# Clocking.net
KiCad netlist of a schematic drawn in Altium Designer
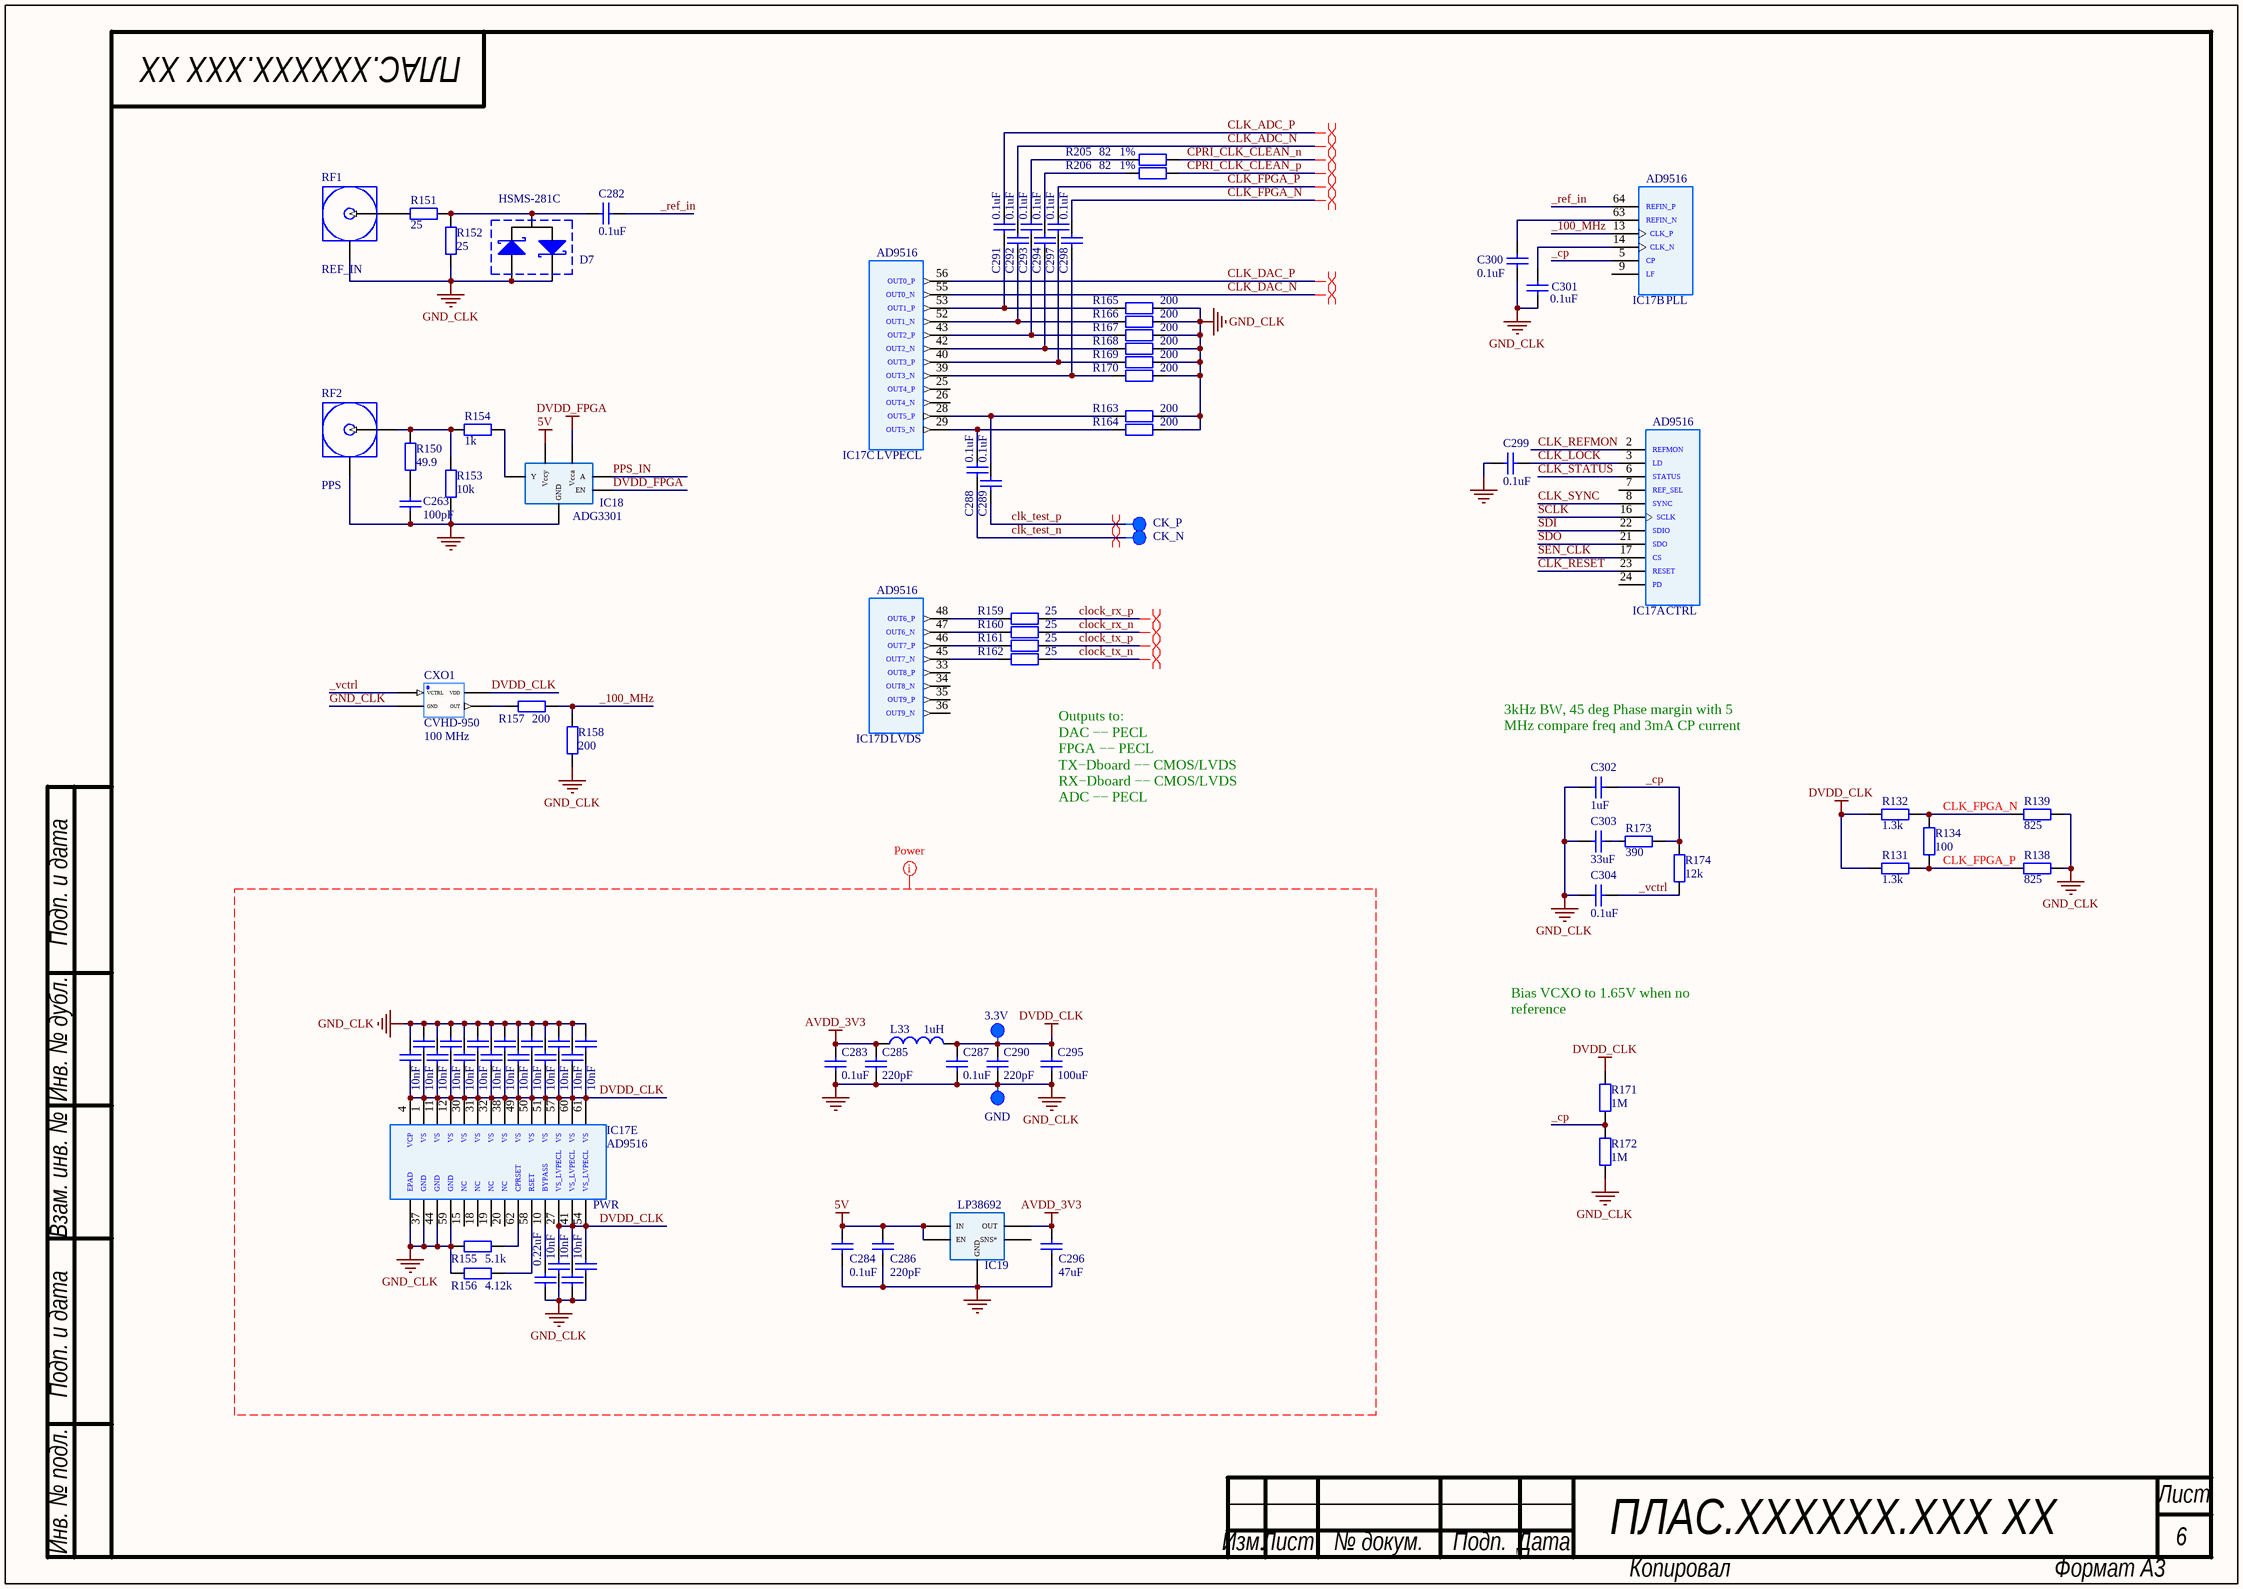
[diagram p0: Clocking.SchDoc]

(export (version "E")
  (design (tool "Eeschema 10.0.6"))
  (components
    (comp (ref "C263")
      (value "100pF")
      (footprint "С0402")
      (description "Cer Cap Small")
      (fields (field (name "MANUFACTURER") "Murata") (field (name "VOLTAGE") "16V"))
      (libsource (lib "") (part "Cer Cap_1"))
    )
    (comp (ref "C264")
      (value "10nF")
      (footprint "С0402")
      (description "Cer Cap Small")
      (fields (field (name "MANUFACTURER") "Murata") (field (name "VOLTAGE") "25V"))
      (libsource (lib "USRP2_Clone") (part "Cer Cap"))
    )
    (comp (ref "C265")
      (value "10nF")
      (footprint "С0402")
      (description "Cer Cap Small")
      (fields (field (name "MANUFACTURER") "Murata") (field (name "VOLTAGE") "25V"))
      (libsource (lib "USRP2_Clone") (part "Cer Cap"))
    )
    (comp (ref "C266")
      (value "10nF")
      (footprint "С0402")
      (description "Cer Cap Small")
      (fields (field (name "MANUFACTURER") "Murata") (field (name "VOLTAGE") "25V"))
      (libsource (lib "USRP2_Clone") (part "Cer Cap"))
    )
    (comp (ref "C267")
      (value "10nF")
      (footprint "С0402")
      (description "Cer Cap Small")
      (fields (field (name "MANUFACTURER") "Murata") (field (name "VOLTAGE") "25V"))
      (libsource (lib "USRP2_Clone") (part "Cer Cap"))
    )
    (comp (ref "C268")
      (value "10nF")
      (footprint "С0402")
      (description "Cer Cap Small")
      (fields (field (name "MANUFACTURER") "Murata") (field (name "VOLTAGE") "25V"))
      (libsource (lib "USRP2_Clone") (part "Cer Cap"))
    )
    (comp (ref "C269")
      (value "10nF")
      (footprint "С0402")
      (description "Cer Cap Small")
      (fields (field (name "MANUFACTURER") "Murata") (field (name "VOLTAGE") "25V"))
      (libsource (lib "USRP2_Clone") (part "Cer Cap"))
    )
    (comp (ref "C270")
      (value "10nF")
      (footprint "С0402")
      (description "Cer Cap Small")
      (fields (field (name "MANUFACTURER") "Murata") (field (name "VOLTAGE") "25V"))
      (libsource (lib "USRP2_Clone") (part "Cer Cap"))
    )
    (comp (ref "C271")
      (value "10nF")
      (footprint "С0402")
      (description "Cer Cap Small")
      (fields (field (name "MANUFACTURER") "Murata") (field (name "VOLTAGE") "25V"))
      (libsource (lib "USRP2_Clone") (part "Cer Cap"))
    )
    (comp (ref "C272")
      (value "10nF")
      (footprint "С0402")
      (description "Cer Cap Small")
      (fields (field (name "MANUFACTURER") "Murata") (field (name "VOLTAGE") "25V"))
      (libsource (lib "USRP2_Clone") (part "Cer Cap"))
    )
    (comp (ref "C273")
      (value "10nF")
      (footprint "С0402")
      (description "Cer Cap Small")
      (fields (field (name "MANUFACTURER") "Murata") (field (name "VOLTAGE") "25V"))
      (libsource (lib "USRP2_Clone") (part "Cer Cap"))
    )
    (comp (ref "C274")
      (value "10nF")
      (footprint "С0402")
      (description "Cer Cap Small")
      (fields (field (name "MANUFACTURER") "Murata") (field (name "VOLTAGE") "25V"))
      (libsource (lib "USRP2_Clone") (part "Cer Cap"))
    )
    (comp (ref "C275")
      (value "0.22uF")
      (footprint "С0402")
      (description "Cer Cap Small")
      (fields (field (name "MANUFACTURER") "Murata") (field (name "VOLTAGE") "16V"))
      (libsource (lib "USRP2_Clone") (part "Cer Cap"))
    )
    (comp (ref "C276")
      (value "10nF")
      (footprint "С0402")
      (description "Cer Cap Small")
      (fields (field (name "MANUFACTURER") "Murata") (field (name "VOLTAGE") "25V"))
      (libsource (lib "USRP2_Clone") (part "Cer Cap"))
    )
    (comp (ref "C277")
      (value "10nF")
      (footprint "С0402")
      (description "Cer Cap Small")
      (fields (field (name "MANUFACTURER") "Murata") (field (name "VOLTAGE") "25V"))
      (libsource (lib "USRP2_Clone") (part "Cer Cap"))
    )
    (comp (ref "C278")
      (value "10nF")
      (footprint "С0402")
      (description "Cer Cap Small")
      (fields (field (name "MANUFACTURER") "Murata") (field (name "VOLTAGE") "25V"))
      (libsource (lib "USRP2_Clone") (part "Cer Cap"))
    )
    (comp (ref "C279")
      (value "10nF")
      (footprint "С0402")
      (description "Cer Cap Small")
      (fields (field (name "MANUFACTURER") "Murata") (field (name "VOLTAGE") "25V"))
      (libsource (lib "USRP2_Clone") (part "Cer Cap"))
    )
    (comp (ref "C280")
      (value "10nF")
      (footprint "С0402")
      (description "Cer Cap Small")
      (fields (field (name "MANUFACTURER") "Murata") (field (name "VOLTAGE") "25V"))
      (libsource (lib "USRP2_Clone") (part "Cer Cap"))
    )
    (comp (ref "C281")
      (value "10nF")
      (footprint "С0402")
      (description "Cer Cap Small")
      (fields (field (name "MANUFACTURER") "Murata") (field (name "VOLTAGE") "25V"))
      (libsource (lib "USRP2_Clone") (part "Cer Cap"))
    )
    (comp (ref "C282")
      (value "0.1uF")
      (footprint "С0402")
      (description "Cer Cap Small")
      (fields (field (name "MANUFACTURER") "Murata") (field (name "VOLTAGE") "16V"))
      (libsource (lib "") (part "Cer Cap_1"))
    )
    (comp (ref "C283")
      (value "0.1uF")
      (footprint "C0603")
      (description "Cer Cap Small")
      (fields (field (name "MANUFACTURER") "Murata") (field (name "VOLTAGE") "16V"))
      (libsource (lib "USRP2_Clone") (part "Cer Cap"))
    )
    (comp (ref "C284")
      (value "0.1uF")
      (footprint "C0603")
      (description "Cer Cap Small")
      (fields (field (name "MANUFACTURER") "Murata") (field (name "VOLTAGE") "16V"))
      (libsource (lib "USRP2_Clone") (part "Cer Cap"))
    )
    (comp (ref "C285")
      (value "220pF")
      (footprint "C0603")
      (description "Cer Cap Small")
      (fields (field (name "MANUFACTURER") "Murata") (field (name "VOLTAGE") "16V"))
      (libsource (lib "USRP2_Clone") (part "Cer Cap"))
    )
    (comp (ref "C286")
      (value "220pF")
      (footprint "C0603")
      (description "Cer Cap Small")
      (fields (field (name "MANUFACTURER") "Murata") (field (name "VOLTAGE") "16V"))
      (libsource (lib "USRP2_Clone") (part "Cer Cap"))
    )
    (comp (ref "C287")
      (value "0.1uF")
      (footprint "C0603")
      (description "Cer Cap Small")
      (fields (field (name "MANUFACTURER") "Murata") (field (name "VOLTAGE") "16V"))
      (libsource (lib "USRP2_Clone") (part "Cer Cap"))
    )
    (comp (ref "C288")
      (value "0.1uF")
      (footprint "С0402")
      (description "Cer Cap Small")
      (fields (field (name "MANUFACTURER") "Murata") (field (name "VOLTAGE") "16V"))
      (libsource (lib "") (part "Cer Cap_1"))
    )
    (comp (ref "C289")
      (value "0.1uF")
      (footprint "С0402")
      (description "Cer Cap Small")
      (fields (field (name "MANUFACTURER") "Murata") (field (name "VOLTAGE") "16V"))
      (libsource (lib "") (part "Cer Cap_1"))
    )
    (comp (ref "C290")
      (value "220pF")
      (footprint "C0603")
      (description "Cer Cap Small")
      (fields (field (name "MANUFACTURER") "Murata") (field (name "VOLTAGE") "16V"))
      (libsource (lib "USRP2_Clone") (part "Cer Cap"))
    )
    (comp (ref "C291")
      (value "0.1uF")
      (footprint "С0402")
      (description "Cer Cap Small")
      (fields (field (name "MANUFACTURER") "Murata") (field (name "VOLTAGE") "16V"))
      (libsource (lib "") (part "Cer Cap_1"))
    )
    (comp (ref "C292")
      (value "0.1uF")
      (footprint "С0402")
      (description "Cer Cap Small")
      (fields (field (name "MANUFACTURER") "Murata") (field (name "VOLTAGE") "16V"))
      (libsource (lib "") (part "Cer Cap_1"))
    )
    (comp (ref "C293")
      (value "0.1uF")
      (footprint "С0402")
      (description "Cer Cap Small")
      (fields (field (name "MANUFACTURER") "Murata") (field (name "VOLTAGE") "16V"))
      (libsource (lib "") (part "Cer Cap_1"))
    )
    (comp (ref "C294")
      (value "0.1uF")
      (footprint "С0402")
      (description "Cer Cap Small")
      (fields (field (name "MANUFACTURER") "Murata") (field (name "VOLTAGE") "16V"))
      (libsource (lib "") (part "Cer Cap_1"))
    )
    (comp (ref "C295")
      (value "100uF")
      (footprint "C1210")
      (description "Cer Cap Large")
      (fields (field (name "MANUFACTURER") "Murata") (field (name "TOLERANCE") "20%"))
      (libsource (lib "") (part "Cap uF_1"))
    )
    (comp (ref "C296")
      (value "47uF")
      (footprint "C1210")
      (description "Cer Cap Large")
      (fields (field (name "MANUFACTURER") "Murata") (field (name "TOLERANCE") "20%"))
      (libsource (lib "USRP2_Clone") (part "Cap uF"))
    )
    (comp (ref "C297")
      (value "0.1uF")
      (footprint "С0402")
      (description "Cer Cap Small")
      (fields (field (name "MANUFACTURER") "Murata") (field (name "VOLTAGE") "16V"))
      (libsource (lib "") (part "Cer Cap_1"))
    )
    (comp (ref "C298")
      (value "0.1uF")
      (footprint "С0402")
      (description "Cer Cap Small")
      (fields (field (name "MANUFACTURER") "Murata") (field (name "VOLTAGE") "16V"))
      (libsource (lib "") (part "Cer Cap_1"))
    )
    (comp (ref "C299")
      (value "0.1uF")
      (footprint "С0402")
      (description "Cer Cap Small")
      (fields (field (name "MANUFACTURER") "Murata") (field (name "VOLTAGE") "16V"))
      (libsource (lib "USRP2_Clone") (part "Cer Cap"))
    )
    (comp (ref "C300")
      (value "0.1uF")
      (footprint "С0402")
      (description "Cer Cap Small")
      (fields (field (name "MANUFACTURER") "Murata") (field (name "VOLTAGE") "16V"))
      (libsource (lib "") (part "Cer Cap_1"))
    )
    (comp (ref "C301")
      (value "0.1uF")
      (footprint "С0402")
      (description "Cer Cap Small")
      (fields (field (name "MANUFACTURER") "Murata") (field (name "VOLTAGE") "16V"))
      (libsource (lib "USRP2_Clone") (part "Cer Cap"))
    )
    (comp (ref "C302")
      (value "1uF")
      (footprint "C0603")
      (description "Cer Cap Small")
      (fields (field (name "MANUFACTURER") "Murata") (field (name "VOLTAGE") "10V"))
      (libsource (lib "USRP2_Clone") (part "Cer Cap"))
    )
    (comp (ref "C303")
      (value "33uF")
      (footprint "C1210")
      (description "Cer Cap Large")
      (fields (field (name "MANUFACTURER") "Murata") (field (name "TOLERANCE") "20%"))
      (libsource (lib "USRP2_Clone") (part "Cap uF"))
    )
    (comp (ref "C304")
      (value "0.1uF")
      (footprint "C0603")
      (description "Cer Cap Small")
      (fields (field (name "MANUFACTURER") "Murata") (field (name "VOLTAGE") "16V"))
      (libsource (lib "USRP2_Clone") (part "Cer Cap"))
    )
    (comp (ref "CP9")
      (value "3.3V")
      (footprint "Control Point")
      (description "Control Point")
      (libsource (lib "USRP2_Clone") (part "Control Point"))
    )
    (comp (ref "CP10")
      (value "GND")
      (footprint "Control Point")
      (description "Control Point")
      (libsource (lib "USRP2_Clone") (part "Control Point"))
    )
    (comp (ref "CP11")
      (value "CK_P")
      (footprint "Control Point")
      (description "Control Point")
      (libsource (lib "USRP2_Clone") (part "Control Point"))
    )
    (comp (ref "CP12")
      (value "CK_N")
      (footprint "Control Point")
      (description "Control Point")
      (libsource (lib "USRP2_Clone") (part "Control Point"))
    )
    (comp (ref "CXO1")
      (value "CVHD-950")
      (footprint "CVHD-950")
      (description "Crystal Oscillator")
      (fields (field (name "VOLTAGE") "3.3V ±0.3V") (field (name "FREQUENCY") "100 MHz"))
      (libsource (lib "USRP2_Clone") (part "CVHD-950"))
    )
    (comp (ref "D7")
      (value "HSMS-281C")
      (footprint "SOT-323")
      (description "RF Schottky Barrier Diodes")
      (libsource (lib "USRP2_Clone") (part "HSMS-281x"))
    )
    (comp (ref "IC17")
      (value "AD9516")
      (footprint "LFCSP-64")
      (description "14-Output Clock Generator")
      (fields (field (name "VOLTAGE") "2.5 V to 3.3 V"))
      (libsource (lib "USRP2_Clone") (part "AD9516"))
    )
    (comp (ref "IC18")
      (value "ADG3301")
      (footprint "SOT-23-6")
      (description "Bidirectional Logic Level Translator")
      (fields (field (name "VOLTAGE") "1.15 V to 5.5 V"))
      (libsource (lib "USRP2_Clone") (part "ADG3301"))
    )
    (comp (ref "IC19")
      (value "LP38692")
      (footprint "SOT-223-5")
      (description "Linear Regulator")
      (libsource (lib "USRP2_Clone") (part "LP38692"))
    )
    (comp (ref "L33")
      (value "1uH")
      (footprint "L1210_Murata")
      (description "Inductor_Power_Lines")
      (fields (field (name "TOLERANCE") "5%") (field (name "MANUFACTURER") "Murata"))
      (libsource (lib "USRP2_Clone") (part "Inductor_LF"))
    )
    (comp (ref "R131")
      (value "1.3k")
      (footprint "R0402")
      (description "Resistor")
      (fields (field (name "TOLERANCE") "5%") (field (name "POWER") "0.062 Wt"))
      (libsource (lib "") (part "Res_2"))
    )
    (comp (ref "R132")
      (value "1.3k")
      (footprint "R0402")
      (description "Resistor")
      (fields (field (name "TOLERANCE") "5%") (field (name "POWER") "0.062 Wt"))
      (libsource (lib "") (part "Res_2"))
    )
    (comp (ref "R134")
      (value "100")
      (footprint "R0402")
      (description "Resistor")
      (fields (field (name "TOLERANCE") "5%") (field (name "POWER") "0.062 Wt"))
      (libsource (lib "") (part "Res_6"))
    )
    (comp (ref "R138")
      (value "825")
      (footprint "R0402")
      (description "Resistor")
      (fields (field (name "TOLERANCE") "5%") (field (name "POWER") "0.062 Wt"))
      (libsource (lib "") (part "Res_2"))
    )
    (comp (ref "R139")
      (value "825")
      (footprint "R0402")
      (description "Resistor")
      (fields (field (name "TOLERANCE") "5%") (field (name "POWER") "0.062 Wt"))
      (libsource (lib "") (part "Res_1"))
    )
    (comp (ref "R150")
      (value "49.9")
      (footprint "R0402")
      (description "Resistor")
      (fields (field (name "TOLERANCE") "5%") (field (name "POWER") "0.062 Wt"))
      (libsource (lib "USRP2_Clone") (part "Res"))
    )
    (comp (ref "R151")
      (value "25")
      (footprint "R0402")
      (description "Resistor")
      (fields (field (name "TOLERANCE") "5%") (field (name "POWER") "0.062 Wt"))
      (libsource (lib "") (part "Res_1"))
    )
    (comp (ref "R152")
      (value "25")
      (footprint "R0402")
      (description "Resistor")
      (fields (field (name "TOLERANCE") "5%") (field (name "POWER") "0.062 Wt"))
      (libsource (lib "") (part "Res_3"))
    )
    (comp (ref "R153")
      (value "10k")
      (footprint "R0402")
      (description "Resistor")
      (fields (field (name "TOLERANCE") "5%") (field (name "POWER") "0.062 Wt"))
      (libsource (lib "USRP2_Clone") (part "Res"))
    )
    (comp (ref "R154")
      (value "1k")
      (footprint "R0402")
      (description "Resistor")
      (fields (field (name "TOLERANCE") "5%") (field (name "POWER") "0.062 Wt"))
      (libsource (lib "") (part "Res_1"))
    )
    (comp (ref "R155")
      (value "5.1k")
      (footprint "R0402")
      (description "Resistor")
      (fields (field (name "TOLERANCE") "5%") (field (name "POWER") "0.062 Wt"))
      (libsource (lib "USRP2_Clone") (part "Res"))
    )
    (comp (ref "R156")
      (value "4.12k")
      (footprint "R0402")
      (description "Resistor")
      (fields (field (name "TOLERANCE") "5%") (field (name "POWER") "0.062 Wt"))
      (libsource (lib "USRP2_Clone") (part "Res"))
    )
    (comp (ref "R157")
      (value "200")
      (footprint "R0402")
      (description "Resistor")
      (fields (field (name "TOLERANCE") "5%") (field (name "POWER") "0.062 Wt"))
      (libsource (lib "") (part "Res_1"))
    )
    (comp (ref "R158")
      (value "200")
      (footprint "R0402")
      (description "Resistor")
      (fields (field (name "TOLERANCE") "5%") (field (name "POWER") "0.062 Wt"))
      (libsource (lib "") (part "Res_4"))
    )
    (comp (ref "R159")
      (value "25")
      (footprint "R0402")
      (description "Resistor")
      (fields (field (name "TOLERANCE") "5%") (field (name "POWER") "0.062 Wt"))
      (libsource (lib "") (part "Res_1"))
    )
    (comp (ref "R160")
      (value "25")
      (footprint "R0402")
      (description "Resistor")
      (fields (field (name "TOLERANCE") "5%") (field (name "POWER") "0.062 Wt"))
      (libsource (lib "") (part "Res_1"))
    )
    (comp (ref "R161")
      (value "25")
      (footprint "R0402")
      (description "Resistor")
      (fields (field (name "TOLERANCE") "5%") (field (name "POWER") "0.062 Wt"))
      (libsource (lib "") (part "Res_1"))
    )
    (comp (ref "R162")
      (value "25")
      (footprint "R0402")
      (description "Resistor")
      (fields (field (name "TOLERANCE") "5%") (field (name "POWER") "0.062 Wt"))
      (libsource (lib "") (part "Res_1"))
    )
    (comp (ref "R163")
      (value "200")
      (footprint "R0402")
      (description "Resistor")
      (fields (field (name "TOLERANCE") "5%") (field (name "POWER") "0.062 Wt"))
      (libsource (lib "") (part "Res_1"))
    )
    (comp (ref "R164")
      (value "200")
      (footprint "R0402")
      (description "Resistor")
      (fields (field (name "TOLERANCE") "5%") (field (name "POWER") "0.062 Wt"))
      (libsource (lib "") (part "Res_1"))
    )
    (comp (ref "R165")
      (value "200")
      (footprint "R0402")
      (description "Resistor")
      (fields (field (name "TOLERANCE") "5%") (field (name "POWER") "0.062 Wt"))
      (libsource (lib "") (part "Res_1"))
    )
    (comp (ref "R166")
      (value "200")
      (footprint "R0402")
      (description "Resistor")
      (fields (field (name "TOLERANCE") "5%") (field (name "POWER") "0.062 Wt"))
      (libsource (lib "") (part "Res_1"))
    )
    (comp (ref "R167")
      (value "200")
      (footprint "R0402")
      (description "Resistor")
      (fields (field (name "TOLERANCE") "5%") (field (name "POWER") "0.062 Wt"))
      (libsource (lib "") (part "Res_1"))
    )
    (comp (ref "R168")
      (value "200")
      (footprint "R0402")
      (description "Resistor")
      (fields (field (name "TOLERANCE") "5%") (field (name "POWER") "0.062 Wt"))
      (libsource (lib "") (part "Res_1"))
    )
    (comp (ref "R169")
      (value "200")
      (footprint "R0402")
      (description "Resistor")
      (fields (field (name "TOLERANCE") "5%") (field (name "POWER") "0.062 Wt"))
      (libsource (lib "") (part "Res_1"))
    )
    (comp (ref "R170")
      (value "200")
      (footprint "R0402")
      (description "Resistor")
      (fields (field (name "TOLERANCE") "5%") (field (name "POWER") "0.062 Wt"))
      (libsource (lib "") (part "Res_1"))
    )
    (comp (ref "R171")
      (value "1M")
      (footprint "R0402")
      (description "Resistor")
      (fields (field (name "TOLERANCE") "5%") (field (name "POWER") "0.062 Wt"))
      (libsource (lib "") (part "Res_1"))
    )
    (comp (ref "R172")
      (value "1M")
      (footprint "R0402")
      (description "Resistor")
      (fields (field (name "TOLERANCE") "5%") (field (name "POWER") "0.062 Wt"))
      (libsource (lib "") (part "Res_1"))
    )
    (comp (ref "R173")
      (value "390")
      (footprint "R0402")
      (description "Resistor")
      (fields (field (name "TOLERANCE") "5%") (field (name "POWER") "0.062 Wt"))
      (libsource (lib "") (part "Res_3"))
    )
    (comp (ref "R174")
      (value "12k")
      (footprint "R0402")
      (description "Resistor")
      (fields (field (name "TOLERANCE") "5%") (field (name "POWER") "0.062 Wt"))
      (libsource (lib "") (part "Res_2"))
    )
    (comp (ref "R205")
      (value "82")
      (footprint "R0402")
      (description "Resistor")
      (fields
        (field (name "TOLERANCE") "1%")
        (field (name "POWER") "0.062 Wt")
        (field (name "Comment") "Res")
      )
      (libsource (lib "") (part "Res_2"))
    )
    (comp (ref "R206")
      (value "82")
      (footprint "R0402")
      (description "Resistor")
      (fields
        (field (name "TOLERANCE") "1%")
        (field (name "POWER") "0.062 Wt")
        (field (name "Comment") "Res")
      )
      (libsource (lib "") (part "Res_5"))
    )
    (comp (ref "RF1")
      (value "REF_IN")
      (footprint "SMA Angle Female With Term")
      (description "SMA Male Right-Angle PCM Connector")
      (libsource (lib "USRP2_Clone") (part "SMA Angle Female"))
    )
    (comp (ref "RF2")
      (value "PPS")
      (footprint "SMA Angle Female With Term")
      (description "SMA Male Right-Angle PCM Connector")
      (libsource (lib "USRP2_Clone") (part "SMA Angle Female"))
    )
  )
  (nets
    (net (code "1") (name "/CLK_ADC_N") (class "Default")
      (node (ref "C292") (pin "1") (pinfunction "1_1") (pintype "passive"))
    )
    (net (code "2") (name "/CLK_ADC_P") (class "Default")
      (node (ref "C291") (pin "1") (pinfunction "1_1") (pintype "passive"))
    )
    (net (code "3") (name "/CLK_DAC_N") (class "Default")
      (node (ref "IC17") (pin "55") (pinfunction "OUT0_N_55") (pintype "output"))
    )
    (net (code "4") (name "/CLK_DAC_P") (class "Default")
      (node (ref "IC17") (pin "56") (pinfunction "OUT0_P_56") (pintype "output"))
    )
    (net (code "5") (name "/CLK_FPGA_N") (class "Default")
      (node (ref "C298") (pin "1") (pinfunction "1_1") (pintype "passive"))
      (node (ref "R132") (pin "2") (pinfunction "2_2") (pintype "passive"))
      (node (ref "R134") (pin "2") (pinfunction "2_2") (pintype "passive"))
      (node (ref "R139") (pin "2") (pinfunction "2_2") (pintype "passive"))
    )
    (net (code "6") (name "/CLK_FPGA_P") (class "Default")
      (node (ref "C297") (pin "1") (pinfunction "1_1") (pintype "passive"))
      (node (ref "R131") (pin "2") (pinfunction "2_2") (pintype "passive"))
      (node (ref "R134") (pin "1") (pinfunction "1_1") (pintype "passive"))
      (node (ref "R138") (pin "1") (pinfunction "1_1") (pintype "passive"))
    )
    (net (code "7") (name "/CLK_LOCK") (class "Default")
      (node (ref "C299") (pin "2") (pinfunction "2_2") (pintype "passive"))
      (node (ref "IC17") (pin "3") (pinfunction "LD_3") (pintype "passive"))
    )
    (net (code "8") (name "/CLK_REFMON") (class "Default")
      (node (ref "IC17") (pin "2") (pinfunction "REFMON_2") (pintype "passive"))
    )
    (net (code "9") (name "/CLK_RESET") (class "Default")
      (node (ref "IC17") (pin "23") (pinfunction "RESET_23") (pintype "passive"))
    )
    (net (code "10") (name "/CLK_STATUS") (class "Default")
      (node (ref "IC17") (pin "6") (pinfunction "STATUS_6") (pintype "passive"))
    )
    (net (code "11") (name "/CLK_SYNC") (class "Default")
      (node (ref "IC17") (pin "8") (pinfunction "SYNC_8") (pintype "passive"))
    )
    (net (code "12") (name "/CPRI_CLK_CLEAN_n") (class "Default")
      (node (ref "R205") (pin "2") (pinfunction "2_2") (pintype "passive"))
    )
    (net (code "13") (name "/CPRI_CLK_CLEAN_p") (class "Default")
      (node (ref "R206") (pin "2") (pinfunction "2_2") (pintype "passive"))
    )
    (net (code "14") (name "/PPS_IN") (class "Default")
      (node (ref "IC18") (pin "2") (pinfunction "A_2") (pintype "passive"))
    )
    (net (code "15") (name "/SCLK") (class "Default")
      (node (ref "IC17") (pin "16") (pinfunction "SCLK_16") (pintype "passive"))
    )
    (net (code "16") (name "/SDI") (class "Default")
      (node (ref "IC17") (pin "22") (pinfunction "SDIO_22") (pintype "passive"))
    )
    (net (code "17") (name "/SDO") (class "Default")
      (node (ref "IC17") (pin "21") (pinfunction "SDO_21") (pintype "passive"))
    )
    (net (code "18") (name "/SEN_CLK") (class "Default")
      (node (ref "IC17") (pin "17") (pinfunction "CS_17") (pintype "passive"))
    )
    (net (code "19") (name "/_100_MHz") (class "Default")
      (node (ref "IC17") (pin "13") (pinfunction "CLK_P_13") (pintype "passive"))
      (node (ref "R157") (pin "1") (pinfunction "1_1") (pintype "passive"))
      (node (ref "R158") (pin "1") (pinfunction "1_1") (pintype "passive"))
    )
    (net (code "20") (name "/_cp") (class "Default")
      (node (ref "C302") (pin "2") (pinfunction "2_2") (pintype "passive"))
      (node (ref "IC17") (pin "5") (pinfunction "CP_5") (pintype "passive"))
      (node (ref "R171") (pin "2") (pinfunction "2_2") (pintype "passive"))
      (node (ref "R172") (pin "1") (pinfunction "1_1") (pintype "passive"))
      (node (ref "R173") (pin "1") (pinfunction "1_1") (pintype "passive"))
      (node (ref "R174") (pin "2") (pinfunction "2_2") (pintype "passive"))
    )
    (net (code "21") (name "/_ref_in") (class "Default")
      (node (ref "C282") (pin "1") (pinfunction "1_1") (pintype "passive"))
      (node (ref "IC17") (pin "64") (pinfunction "REFIN_P_64") (pintype "passive"))
    )
    (net (code "22") (name "/_vctrl") (class "Default")
      (node (ref "C304") (pin "2") (pinfunction "2_2") (pintype "passive"))
      (node (ref "CXO1") (pin "1") (pinfunction "VCTRL_1") (pintype "input"))
      (node (ref "R174") (pin "1") (pinfunction "1_1") (pintype "passive"))
    )
    (net (code "23") (name "/clk_test_n") (class "Default")
      (node (ref "C288") (pin "2") (pinfunction "2_2") (pintype "passive"))
      (node (ref "CP12") (pin "1") (pinfunction "1_1") (pintype "passive"))
    )
    (net (code "24") (name "/clk_test_p") (class "Default")
      (node (ref "C289") (pin "2") (pinfunction "2_2") (pintype "passive"))
      (node (ref "CP11") (pin "1") (pinfunction "1_1") (pintype "passive"))
    )
    (net (code "25") (name "/clock_rx_n") (class "Default")
      (node (ref "R160") (pin "1") (pinfunction "1_1") (pintype "passive"))
    )
    (net (code "26") (name "/clock_rx_p") (class "Default")
      (node (ref "R159") (pin "1") (pinfunction "1_1") (pintype "passive"))
    )
    (net (code "27") (name "/clock_tx_n") (class "Default")
      (node (ref "R162") (pin "1") (pinfunction "1_1") (pintype "passive"))
    )
    (net (code "28") (name "/clock_tx_p") (class "Default")
      (node (ref "R161") (pin "1") (pinfunction "1_1") (pintype "passive"))
    )
    (net (code "29") (name "5V") (class "Default")
      (node (ref "C284") (pin "1") (pinfunction "1_1") (pintype "passive"))
      (node (ref "C286") (pin "1") (pinfunction "1_1") (pintype "passive"))
      (node (ref "IC18") (pin "6") (pinfunction "Vccy_6") (pintype "passive"))
      (node (ref "IC19") (pin "1") (pinfunction "EN_1") (pintype "passive"))
      (node (ref "IC19") (pin "4") (pinfunction "IN_4") (pintype "passive"))
    )
    (net (code "30") (name "AVDD_3V3") (class "Default")
      (node (ref "C283") (pin "1") (pinfunction "1_1") (pintype "passive"))
      (node (ref "C285") (pin "1") (pinfunction "1_1") (pintype "passive"))
      (node (ref "C296") (pin "1") (pinfunction "1_1") (pintype "passive"))
      (node (ref "IC19") (pin "3") (pinfunction "OUT_3") (pintype "passive"))
      (node (ref "L33") (pin "2") (pinfunction "2_2") (pintype "passive"))
    )
    (net (code "31") (name "DVDD_CLK") (class "Default")
      (node (ref "C264") (pin "1") (pinfunction "1_1") (pintype "passive"))
      (node (ref "C265") (pin "2") (pinfunction "2_2") (pintype "passive"))
      (node (ref "C266") (pin "1") (pinfunction "1_1") (pintype "passive"))
      (node (ref "C267") (pin "2") (pinfunction "2_2") (pintype "passive"))
      (node (ref "C268") (pin "1") (pinfunction "1_1") (pintype "passive"))
      (node (ref "C269") (pin "2") (pinfunction "2_2") (pintype "passive"))
      (node (ref "C270") (pin "1") (pinfunction "1_1") (pintype "passive"))
      (node (ref "C271") (pin "2") (pinfunction "2_2") (pintype "passive"))
      (node (ref "C272") (pin "1") (pinfunction "1_1") (pintype "passive"))
      (node (ref "C273") (pin "2") (pinfunction "2_2") (pintype "passive"))
      (node (ref "C274") (pin "1") (pinfunction "1_1") (pintype "passive"))
      (node (ref "C276") (pin "2") (pinfunction "2_2") (pintype "passive"))
      (node (ref "C277") (pin "2") (pinfunction "2_2") (pintype "passive"))
      (node (ref "C278") (pin "1") (pinfunction "1_1") (pintype "passive"))
      (node (ref "C279") (pin "2") (pinfunction "2_2") (pintype "passive"))
      (node (ref "C280") (pin "2") (pinfunction "2_2") (pintype "passive"))
      (node (ref "C281") (pin "2") (pinfunction "2_2") (pintype "passive"))
      (node (ref "C287") (pin "1") (pinfunction "1_1") (pintype "passive"))
      (node (ref "C290") (pin "1") (pinfunction "1_1") (pintype "passive"))
      (node (ref "C295") (pin "2") (pinfunction "2_2") (pintype "passive"))
      (node (ref "CP9") (pin "1") (pinfunction "1_1") (pintype "passive"))
      (node (ref "CXO1") (pin "4") (pinfunction "VDD_4") (pintype "passive"))
      (node (ref "IC17") (pin "1") (pinfunction "VS_1") (pintype "power_in"))
      (node (ref "IC17") (pin "11") (pinfunction "VS_11") (pintype "power_in"))
      (node (ref "IC17") (pin "12") (pinfunction "VS_12") (pintype "power_in"))
      (node (ref "IC17") (pin "27") (pinfunction "VS_LVPECL_27") (pintype "power_in"))
      (node (ref "IC17") (pin "30") (pinfunction "VS_30") (pintype "power_in"))
      (node (ref "IC17") (pin "31") (pinfunction "VS_31") (pintype "power_in"))
      (node (ref "IC17") (pin "32") (pinfunction "VS_32") (pintype "power_in"))
      (node (ref "IC17") (pin "38") (pinfunction "VS_38") (pintype "power_in"))
      (node (ref "IC17") (pin "4") (pinfunction "VCP_4") (pintype "power_in"))
      (node (ref "IC17") (pin "41") (pinfunction "VS_LVPECL_41") (pintype "power_in"))
      (node (ref "IC17") (pin "49") (pinfunction "VS_49") (pintype "power_in"))
      (node (ref "IC17") (pin "50") (pinfunction "VS_50") (pintype "power_in"))
      (node (ref "IC17") (pin "51") (pinfunction "VS_51") (pintype "power_in"))
      (node (ref "IC17") (pin "54") (pinfunction "VS_LVPECL_54") (pintype "power_in"))
      (node (ref "IC17") (pin "57") (pinfunction "VS_57") (pintype "power_in"))
      (node (ref "IC17") (pin "60") (pinfunction "VS_60") (pintype "power_in"))
      (node (ref "IC17") (pin "61") (pinfunction "VS_61") (pintype "power_in"))
      (node (ref "L33") (pin "1") (pinfunction "1_1") (pintype "passive"))
      (node (ref "R131") (pin "1") (pinfunction "1_1") (pintype "passive"))
      (node (ref "R132") (pin "1") (pinfunction "1_1") (pintype "passive"))
      (node (ref "R171") (pin "1") (pinfunction "1_1") (pintype "passive"))
    )
    (net (code "32") (name "DVDD_FPGA") (class "Default")
      (node (ref "IC18") (pin "1") (pinfunction "Vcca_1") (pintype "passive"))
      (node (ref "IC18") (pin "4") (pinfunction "EN_4") (pintype "passive"))
    )
    (net (code "33") (name "GND") (class "Default")
      (node (ref "C263") (pin "1") (pinfunction "1_1") (pintype "passive"))
      (node (ref "C264") (pin "2") (pinfunction "2_2") (pintype "passive"))
      (node (ref "C265") (pin "1") (pinfunction "1_1") (pintype "passive"))
      (node (ref "C266") (pin "2") (pinfunction "2_2") (pintype "passive"))
      (node (ref "C267") (pin "1") (pinfunction "1_1") (pintype "passive"))
      (node (ref "C268") (pin "2") (pinfunction "2_2") (pintype "passive"))
      (node (ref "C269") (pin "1") (pinfunction "1_1") (pintype "passive"))
      (node (ref "C270") (pin "2") (pinfunction "2_2") (pintype "passive"))
      (node (ref "C271") (pin "1") (pinfunction "1_1") (pintype "passive"))
      (node (ref "C272") (pin "2") (pinfunction "2_2") (pintype "passive"))
      (node (ref "C273") (pin "1") (pinfunction "1_1") (pintype "passive"))
      (node (ref "C274") (pin "2") (pinfunction "2_2") (pintype "passive"))
      (node (ref "C275") (pin "1") (pinfunction "1_1") (pintype "passive"))
      (node (ref "C276") (pin "1") (pinfunction "1_1") (pintype "passive"))
      (node (ref "C277") (pin "1") (pinfunction "1_1") (pintype "passive"))
      (node (ref "C278") (pin "2") (pinfunction "2_2") (pintype "passive"))
      (node (ref "C279") (pin "1") (pinfunction "1_1") (pintype "passive"))
      (node (ref "C280") (pin "1") (pinfunction "1_1") (pintype "passive"))
      (node (ref "C281") (pin "1") (pinfunction "1_1") (pintype "passive"))
      (node (ref "C283") (pin "2") (pinfunction "2_2") (pintype "passive"))
      (node (ref "C284") (pin "2") (pinfunction "2_2") (pintype "passive"))
      (node (ref "C285") (pin "2") (pinfunction "2_2") (pintype "passive"))
      (node (ref "C286") (pin "2") (pinfunction "2_2") (pintype "passive"))
      (node (ref "C287") (pin "2") (pinfunction "2_2") (pintype "passive"))
      (node (ref "C290") (pin "2") (pinfunction "2_2") (pintype "passive"))
      (node (ref "C295") (pin "1") (pinfunction "1_1") (pintype "passive"))
      (node (ref "C296") (pin "2") (pinfunction "2_2") (pintype "passive"))
      (node (ref "C299") (pin "1") (pinfunction "1_1") (pintype "passive"))
      (node (ref "C300") (pin "2") (pinfunction "2_2") (pintype "passive"))
      (node (ref "C301") (pin "2") (pinfunction "2_2") (pintype "passive"))
      (node (ref "C302") (pin "1") (pinfunction "1_1") (pintype "passive"))
      (node (ref "C303") (pin "2") (pinfunction "2_2") (pintype "passive"))
      (node (ref "C304") (pin "1") (pinfunction "1_1") (pintype "passive"))
      (node (ref "CP10") (pin "1") (pinfunction "1_1") (pintype "passive"))
      (node (ref "CXO1") (pin "2") (pinfunction "GND_2") (pintype "passive"))
      (node (ref "D7") (pin "1") (pinfunction "A_1") (pintype "passive"))
      (node (ref "D7") (pin "2") (pinfunction "K_2") (pintype "passive"))
      (node (ref "IC17") (pin "0") (pinfunction "EPAD_0") (pintype "power_in"))
      (node (ref "IC17") (pin "37") (pinfunction "GND_37") (pintype "power_in"))
      (node (ref "IC17") (pin "44") (pinfunction "GND_44") (pintype "power_in"))
      (node (ref "IC17") (pin "59") (pinfunction "GND_59") (pintype "power_in"))
      (node (ref "IC18") (pin "3") (pinfunction "GND_3") (pintype "passive"))
      (node (ref "IC19") (pin "5") (pinfunction "GND_5") (pintype "passive"))
      (node (ref "R138") (pin "2") (pinfunction "2_2") (pintype "passive"))
      (node (ref "R139") (pin "1") (pinfunction "1_1") (pintype "passive"))
      (node (ref "R152") (pin "2") (pinfunction "2_2") (pintype "passive"))
      (node (ref "R153") (pin "1") (pinfunction "1_1") (pintype "passive"))
      (node (ref "R155") (pin "1") (pinfunction "1_1") (pintype "passive"))
      (node (ref "R156") (pin "1") (pinfunction "1_1") (pintype "passive"))
      (node (ref "R158") (pin "2") (pinfunction "2_2") (pintype "passive"))
      (node (ref "R163") (pin "1") (pinfunction "1_1") (pintype "passive"))
      (node (ref "R164") (pin "1") (pinfunction "1_1") (pintype "passive"))
      (node (ref "R165") (pin "1") (pinfunction "1_1") (pintype "passive"))
      (node (ref "R166") (pin "1") (pinfunction "1_1") (pintype "passive"))
      (node (ref "R167") (pin "1") (pinfunction "1_1") (pintype "passive"))
      (node (ref "R168") (pin "1") (pinfunction "1_1") (pintype "passive"))
      (node (ref "R169") (pin "1") (pinfunction "1_1") (pintype "passive"))
      (node (ref "R170") (pin "1") (pinfunction "1_1") (pintype "passive"))
      (node (ref "R172") (pin "2") (pinfunction "2_2") (pintype "passive"))
      (node (ref "RF1") (pin "0") (pinfunction "GND_0") (pintype "power_in"))
      (node (ref "RF2") (pin "0") (pinfunction "GND_0") (pintype "power_in"))
    )
    (net (code "34") (name "Net-(C263-Pad2)") (class "Default")
      (node (ref "C263") (pin "2") (pinfunction "2_2") (pintype "passive"))
      (node (ref "R150") (pin "1") (pinfunction "1_1") (pintype "passive"))
    )
    (net (code "35") (name "Net-(C282-Pad2)") (class "Default")
      (node (ref "C282") (pin "2") (pinfunction "2_2") (pintype "passive"))
      (node (ref "D7") (pin "3") (pinfunction "K_3") (pintype "passive"))
      (node (ref "R151") (pin "1") (pinfunction "1_1") (pintype "passive"))
      (node (ref "R152") (pin "1") (pinfunction "1_1") (pintype "passive"))
    )
    (net (code "36") (name "Net-(C293-Pad1)") (class "Default")
      (node (ref "C293") (pin "1") (pinfunction "1_1") (pintype "passive"))
      (node (ref "R205") (pin "1") (pinfunction "1_1") (pintype "passive"))
    )
    (net (code "37") (name "Net-(C294-Pad1)") (class "Default")
      (node (ref "C294") (pin "1") (pinfunction "1_1") (pintype "passive"))
      (node (ref "R206") (pin "1") (pinfunction "1_1") (pintype "passive"))
    )
    (net (code "38") (name "Net-(C303-Pad1)") (class "Default")
      (node (ref "C303") (pin "1") (pinfunction "1_1") (pintype "passive"))
      (node (ref "R173") (pin "2") (pinfunction "2_2") (pintype "passive"))
    )
    (net (code "39") (name "Net-(CXO1-OUT)") (class "Default")
      (node (ref "CXO1") (pin "3") (pinfunction "OUT_3") (pintype "output"))
      (node (ref "R157") (pin "2") (pinfunction "2_2") (pintype "passive"))
    )
    (net (code "40") (name "Net-(IC17B-CLK_N)") (class "Default")
      (node (ref "C301") (pin "1") (pinfunction "1_1") (pintype "passive"))
      (node (ref "IC17") (pin "14") (pinfunction "CLK_N_14") (pintype "passive"))
    )
    (net (code "41") (name "Net-(IC17B-REFIN_N)") (class "Default")
      (node (ref "C300") (pin "1") (pinfunction "1_1") (pintype "passive"))
      (node (ref "IC17") (pin "63") (pinfunction "REFIN_N_63") (pintype "passive"))
    )
    (net (code "42") (name "Net-(IC17C-OUT1_N)") (class "Default")
      (node (ref "C292") (pin "2") (pinfunction "2_2") (pintype "passive"))
      (node (ref "IC17") (pin "52") (pinfunction "OUT1_N_52") (pintype "output"))
      (node (ref "R166") (pin "2") (pinfunction "2_2") (pintype "passive"))
    )
    (net (code "43") (name "Net-(IC17C-OUT1_P)") (class "Default")
      (node (ref "C291") (pin "2") (pinfunction "2_2") (pintype "passive"))
      (node (ref "IC17") (pin "53") (pinfunction "OUT1_P_53") (pintype "output"))
      (node (ref "R165") (pin "2") (pinfunction "2_2") (pintype "passive"))
    )
    (net (code "44") (name "Net-(IC17C-OUT2_N)") (class "Default")
      (node (ref "C294") (pin "2") (pinfunction "2_2") (pintype "passive"))
      (node (ref "IC17") (pin "42") (pinfunction "OUT2_N_42") (pintype "output"))
      (node (ref "R168") (pin "2") (pinfunction "2_2") (pintype "passive"))
    )
    (net (code "45") (name "Net-(IC17C-OUT2_P)") (class "Default")
      (node (ref "C293") (pin "2") (pinfunction "2_2") (pintype "passive"))
      (node (ref "IC17") (pin "43") (pinfunction "OUT2_P_43") (pintype "output"))
      (node (ref "R167") (pin "2") (pinfunction "2_2") (pintype "passive"))
    )
    (net (code "46") (name "Net-(IC17C-OUT3_N)") (class "Default")
      (node (ref "C298") (pin "2") (pinfunction "2_2") (pintype "passive"))
      (node (ref "IC17") (pin "39") (pinfunction "OUT3_N_39") (pintype "output"))
      (node (ref "R170") (pin "2") (pinfunction "2_2") (pintype "passive"))
    )
    (net (code "47") (name "Net-(IC17C-OUT3_P)") (class "Default")
      (node (ref "C297") (pin "2") (pinfunction "2_2") (pintype "passive"))
      (node (ref "IC17") (pin "40") (pinfunction "OUT3_P_40") (pintype "output"))
      (node (ref "R169") (pin "2") (pinfunction "2_2") (pintype "passive"))
    )
    (net (code "48") (name "Net-(IC17C-OUT5_N)") (class "Default")
      (node (ref "C288") (pin "1") (pinfunction "1_1") (pintype "passive"))
      (node (ref "IC17") (pin "29") (pinfunction "OUT5_N_29") (pintype "output"))
      (node (ref "R164") (pin "2") (pinfunction "2_2") (pintype "passive"))
    )
    (net (code "49") (name "Net-(IC17C-OUT5_P)") (class "Default")
      (node (ref "C289") (pin "1") (pinfunction "1_1") (pintype "passive"))
      (node (ref "IC17") (pin "28") (pinfunction "OUT5_P_28") (pintype "output"))
      (node (ref "R163") (pin "2") (pinfunction "2_2") (pintype "passive"))
    )
    (net (code "50") (name "Net-(IC17D-OUT6_N)") (class "Default")
      (node (ref "IC17") (pin "47") (pinfunction "OUT6_N_47") (pintype "output"))
      (node (ref "R160") (pin "2") (pinfunction "2_2") (pintype "passive"))
    )
    (net (code "51") (name "Net-(IC17D-OUT6_P)") (class "Default")
      (node (ref "IC17") (pin "48") (pinfunction "OUT6_P_48") (pintype "output"))
      (node (ref "R159") (pin "2") (pinfunction "2_2") (pintype "passive"))
    )
    (net (code "52") (name "Net-(IC17D-OUT7_N)") (class "Default")
      (node (ref "IC17") (pin "45") (pinfunction "OUT7_N_45") (pintype "output"))
      (node (ref "R162") (pin "2") (pinfunction "2_2") (pintype "passive"))
    )
    (net (code "53") (name "Net-(IC17D-OUT7_P)") (class "Default")
      (node (ref "IC17") (pin "46") (pinfunction "OUT7_P_46") (pintype "output"))
      (node (ref "R161") (pin "2") (pinfunction "2_2") (pintype "passive"))
    )
    (net (code "54") (name "Net-(IC17E-BYPASS)") (class "Default")
      (node (ref "C275") (pin "2") (pinfunction "2_2") (pintype "passive"))
      (node (ref "IC17") (pin "10") (pinfunction "BYPASS_10") (pintype "passive"))
    )
    (net (code "55") (name "Net-(IC17E-CPRSET)") (class "Default")
      (node (ref "IC17") (pin "62") (pinfunction "CPRSET_62") (pintype "passive"))
      (node (ref "R155") (pin "2") (pinfunction "2_2") (pintype "passive"))
    )
    (net (code "56") (name "Net-(IC17E-RSET)") (class "Default")
      (node (ref "IC17") (pin "58") (pinfunction "RSET_58") (pintype "passive"))
      (node (ref "R156") (pin "2") (pinfunction "2_2") (pintype "passive"))
    )
    (net (code "57") (name "Net-(IC18-Y)") (class "Default")
      (node (ref "IC18") (pin "5") (pinfunction "Y_5") (pintype "passive"))
      (node (ref "R154") (pin "1") (pinfunction "1_1") (pintype "passive"))
    )
    (net (code "58") (name "Net-(RF1-RF)") (class "Default")
      (node (ref "R151") (pin "2") (pinfunction "2_2") (pintype "passive"))
      (node (ref "RF1") (pin "1") (pinfunction "RF_1") (pintype "input"))
    )
    (net (code "59") (name "Net-(RF2-RF)") (class "Default")
      (node (ref "R150") (pin "2") (pinfunction "2_2") (pintype "passive"))
      (node (ref "R153") (pin "2") (pinfunction "2_2") (pintype "passive"))
      (node (ref "R154") (pin "2") (pinfunction "2_2") (pintype "passive"))
      (node (ref "RF2") (pin "1") (pinfunction "RF_1") (pintype "input"))
    )
    (net (code "60") (name "unconnected-(IC17A-PD-Pad24)") (class "Default")
      (node (ref "IC17") (pin "24") (pinfunction "PD_24") (pintype "passive"))
    )
    (net (code "61") (name "unconnected-(IC17A-REF_SEL-Pad7)") (class "Default")
      (node (ref "IC17") (pin "7") (pinfunction "REF_SEL_7") (pintype "passive"))
    )
    (net (code "62") (name "unconnected-(IC17B-LF-Pad9)") (class "Default")
      (node (ref "IC17") (pin "9") (pinfunction "LF_9") (pintype "passive"))
    )
    (net (code "63") (name "unconnected-(IC17C-OUT4_N-Pad26)") (class "Default")
      (node (ref "IC17") (pin "26") (pinfunction "OUT4_N_26") (pintype "output"))
    )
    (net (code "64") (name "unconnected-(IC17C-OUT4_P-Pad25)") (class "Default")
      (node (ref "IC17") (pin "25") (pinfunction "OUT4_P_25") (pintype "output"))
    )
    (net (code "65") (name "unconnected-(IC17D-OUT8_N-Pad34)") (class "Default")
      (node (ref "IC17") (pin "34") (pinfunction "OUT8_N_34") (pintype "output"))
    )
    (net (code "66") (name "unconnected-(IC17D-OUT8_P-Pad33)") (class "Default")
      (node (ref "IC17") (pin "33") (pinfunction "OUT8_P_33") (pintype "output"))
    )
    (net (code "67") (name "unconnected-(IC17D-OUT9_N-Pad36)") (class "Default")
      (node (ref "IC17") (pin "36") (pinfunction "OUT9_N_36") (pintype "output"))
    )
    (net (code "68") (name "unconnected-(IC17D-OUT9_P-Pad35)") (class "Default")
      (node (ref "IC17") (pin "35") (pinfunction "OUT9_P_35") (pintype "output"))
    )
    (net (code "69") (name "unconnected-(IC17E-NC-Pad15)") (class "Default")
      (node (ref "IC17") (pin "15") (pinfunction "NC_15") (pintype "passive"))
    )
    (net (code "70") (name "unconnected-(IC17E-NC-Pad18)") (class "Default")
      (node (ref "IC17") (pin "18") (pinfunction "NC_18") (pintype "passive"))
    )
    (net (code "71") (name "unconnected-(IC17E-NC-Pad19)") (class "Default")
      (node (ref "IC17") (pin "19") (pinfunction "NC_19") (pintype "passive"))
    )
    (net (code "72") (name "unconnected-(IC17E-NC-Pad20)") (class "Default")
      (node (ref "IC17") (pin "20") (pinfunction "NC_20") (pintype "passive"))
    )
    (net (code "73") (name "unconnected-(IC19-SNS*-Pad6)") (class "Default")
      (node (ref "IC19") (pin "6") (pinfunction "SNS*_6") (pintype "passive"))
    )
  )
)
